# V1.net
KiCad netlist of a schematic drawn in Altium Designer
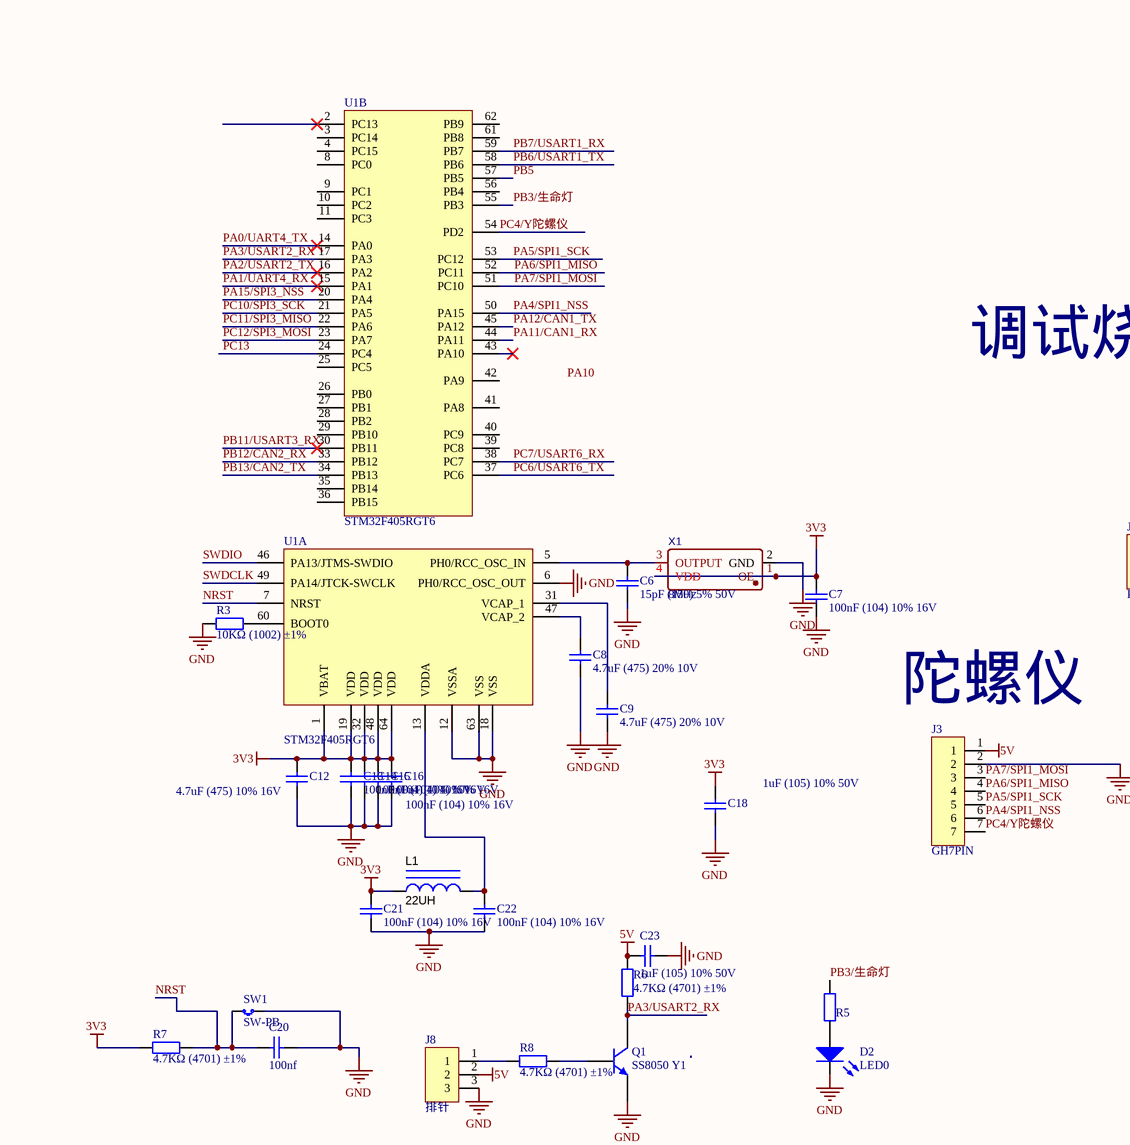
[diagram p0: 英雄云台V1.施佳良.SchDoc, top left]
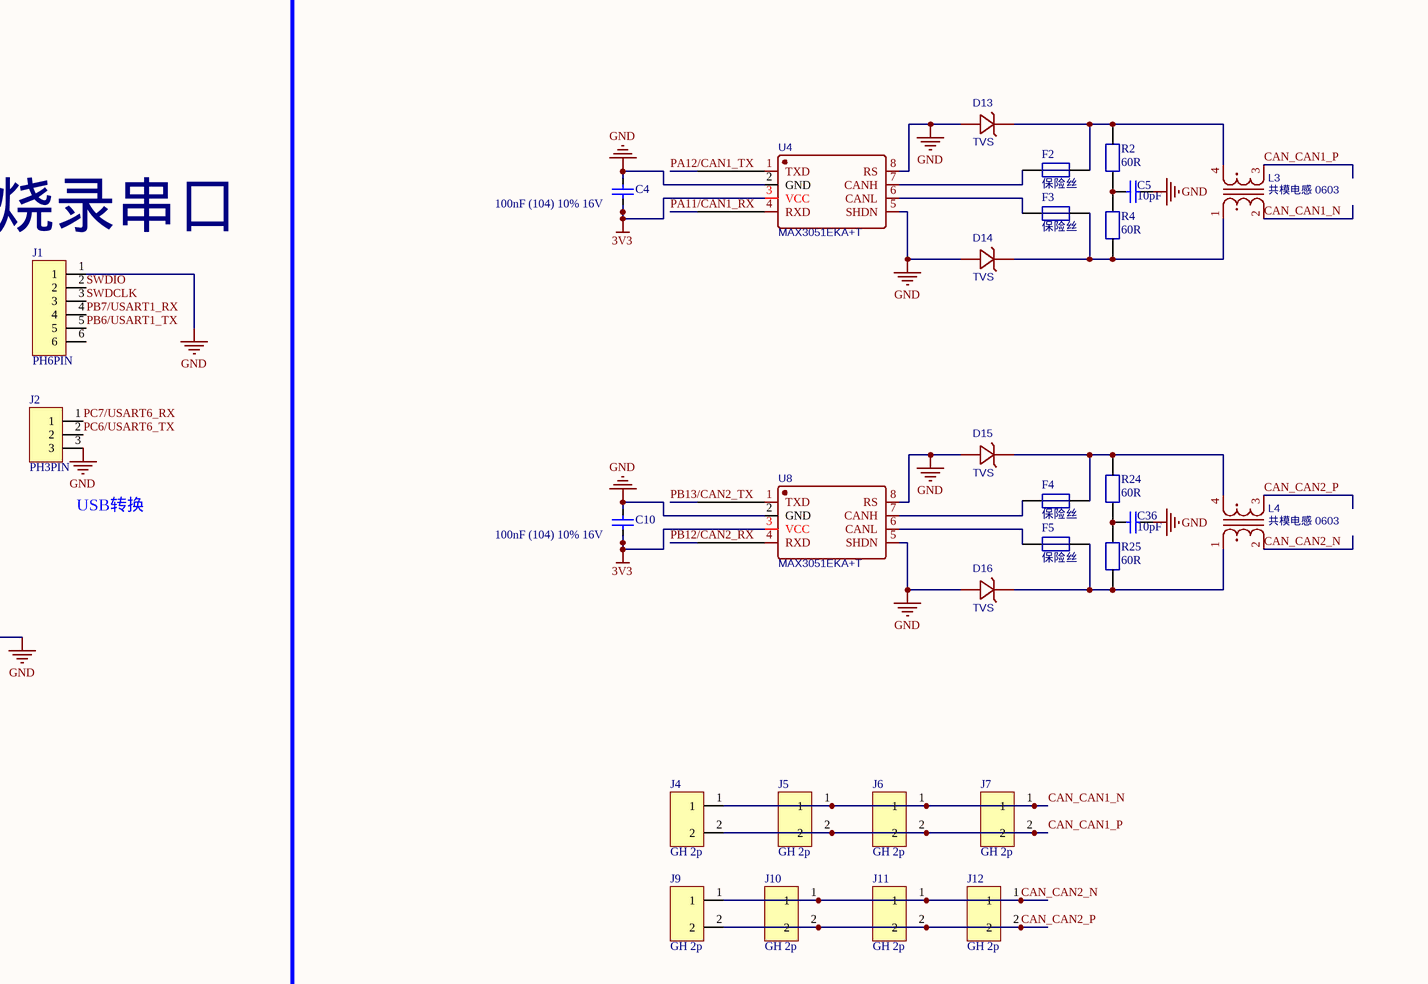
[diagram p1: 英雄云台V1.施佳良.SchDoc, top right]
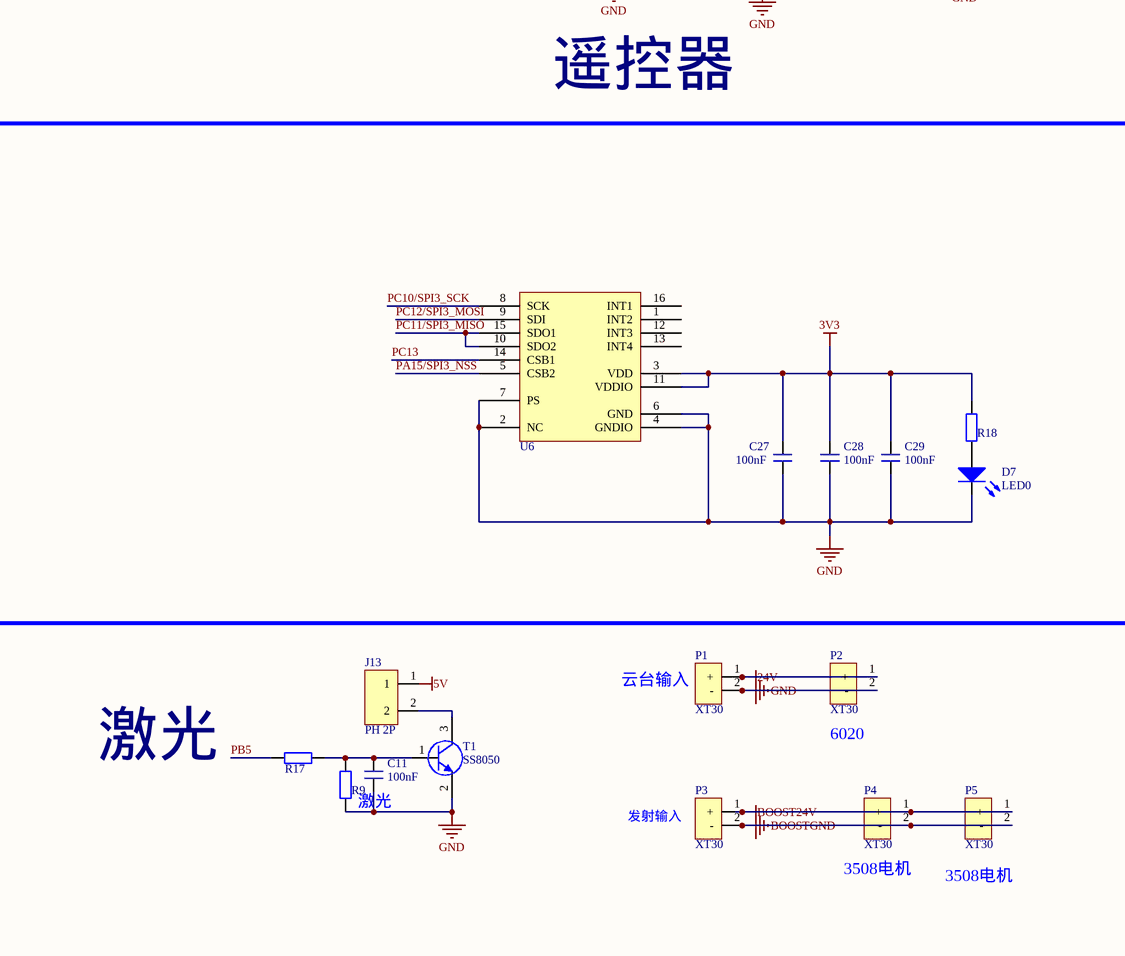
[diagram p2: 英雄云台V1.施佳良.SchDoc, bottom left]
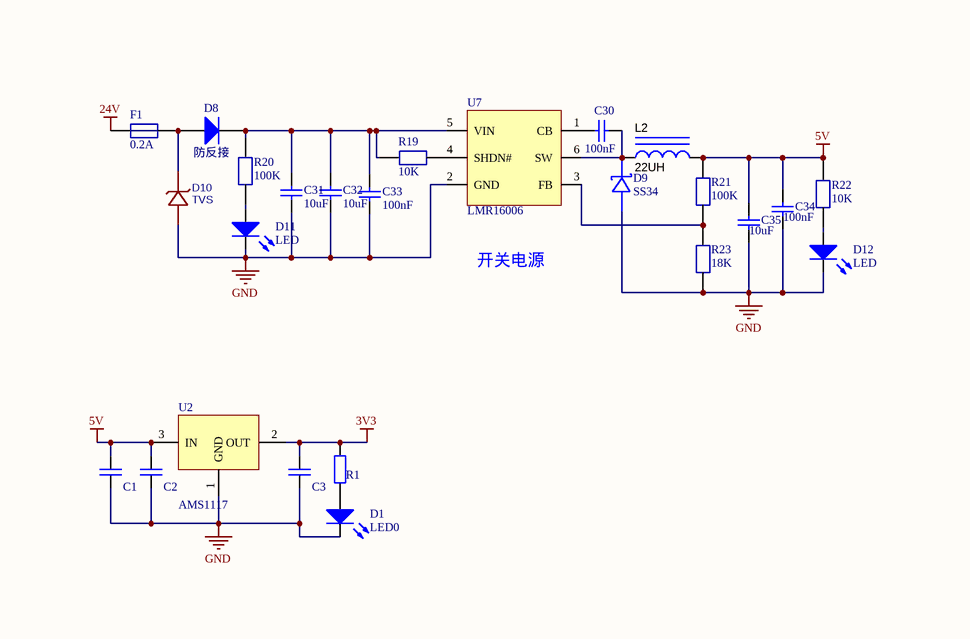
[diagram p3: 英雄云台V1.施佳良.SchDoc, bottom right]

(export (version "E")
  (design (tool "Eeschema 10.0.6"))
  (components
    (comp (ref "C1")
      (value "?uF")
      (footprint "1210_C")
      (fields (field (name "PUBLISHER") "Altium Limited"))
      (libsource (lib "电容-电阻-电感") (part "Cap"))
    )
    (comp (ref "C2")
      (value "?uF")
      (footprint "0603_C")
      (fields (field (name "PUBLISHER") "Altium Limited"))
      (libsource (lib "电容-电阻-电感") (part "Cap"))
    )
    (comp (ref "C3")
      (value "?uF")
      (footprint "1210_C")
      (fields (field (name "PUBLISHER") "Altium Limited"))
      (libsource (lib "电容-电阻-电感") (part "Cap"))
    )
    (comp (ref "C4")
      (value "100nF (104) 10% 16V")
      (footprint "0603_C")
      (description "贴片电容")
      (libsource (lib "Miscellaneous Devices LC") (part "0402 100nF (104) 10% 16V"))
    )
    (comp (ref "C5") (value "10pF") (footprint "0603_C") (libsource (lib "原理图库") (part "C")))
    (comp (ref "C6")
      (value "15pF (150) 5% 50V")
      (footprint "0603_C")
      (description "贴片电容")
      (libsource (lib "Miscellaneous Devices LC") (part "0402 15pF (150) 5% 50V"))
    )
    (comp (ref "C7")
      (value "100nF (104) 10% 16V")
      (footprint "0603_C")
      (description "贴片电容")
      (libsource (lib "Miscellaneous Devices LC") (part "0402 100nF (104) 10% 16V"))
    )
    (comp (ref "C8")
      (value "4.7uF (475) 20% 10V")
      (footprint "0603_C")
      (description "贴片电容")
      (libsource (lib "Miscellaneous Devices LC") (part "0402 4.7uF (475) 20% 10V"))
    )
    (comp (ref "C9")
      (value "4.7uF (475) 20% 10V")
      (footprint "0603_C")
      (description "贴片电容")
      (libsource (lib "Miscellaneous Devices LC") (part "0402 4.7uF (475) 20% 10V"))
    )
    (comp (ref "C10")
      (value "100nF (104) 10% 16V")
      (footprint "0603_C")
      (description "贴片电容")
      (libsource (lib "Miscellaneous Devices LC") (part "0402 100nF (104) 10% 16V"))
    )
    (comp (ref "C11")
      (value "100nF")
      (footprint "0603_C")
      (fields (field (name "PUBLISHER") "Altium Limited"))
      (libsource (lib "USUAUL") (part "Cap"))
    )
    (comp (ref "C12")
      (value "4.7uF (475) 10% 16V")
      (footprint "0603_C")
      (description "贴片电容")
      (libsource (lib "Miscellaneous Devices LC") (part "0603 4.7uF (475) 10% 16V"))
    )
    (comp (ref "C13")
      (value "100nF (104) 10% 16V")
      (footprint "0603_C")
      (description "贴片电容")
      (libsource (lib "Miscellaneous Devices LC") (part "0402 100nF (104) 10% 16V"))
    )
    (comp (ref "C14")
      (value "100nF (104) 10% 16V")
      (footprint "0603_C")
      (description "贴片电容")
      (libsource (lib "Miscellaneous Devices LC") (part "0402 100nF (104) 10% 16V"))
    )
    (comp (ref "C15")
      (value "100nF (104) 10% 16V")
      (footprint "0603_C")
      (description "贴片电容")
      (libsource (lib "Miscellaneous Devices LC") (part "0402 100nF (104) 10% 16V"))
    )
    (comp (ref "C16")
      (value "100nF (104) 10% 16V")
      (footprint "0603_C")
      (description "贴片电容")
      (libsource (lib "Miscellaneous Devices LC") (part "0402 100nF (104) 10% 16V"))
    )
    (comp (ref "C18")
      (value "1uF (105) 10% 50V")
      (footprint "0603_C")
      (description "贴片电容")
      (libsource (lib "Miscellaneous Devices LC") (part "0603 1uF (105) 10% 50V"))
    )
    (comp (ref "C20")
      (value "100nf")
      (footprint "0603_C")
      (description "贴片电容")
      (libsource (lib "Miscellaneous Devices LC") (part "0603 4.7uF (475) 10% 16V"))
    )
    (comp (ref "C21")
      (value "100nF (104) 10% 16V")
      (footprint "0603_C")
      (description "贴片电容")
      (libsource (lib "Miscellaneous Devices LC") (part "0402 100nF (104) 10% 16V"))
    )
    (comp (ref "C22")
      (value "100nF (104) 10% 16V")
      (footprint "0603_C")
      (description "贴片电容")
      (libsource (lib "Miscellaneous Devices LC") (part "0402 100nF (104) 10% 16V"))
    )
    (comp (ref "C23")
      (value "1uF (105) 10% 50V")
      (footprint "0603_C")
      (description "贴片电容")
      (libsource (lib "Miscellaneous Devices LC") (part "0603 1uF (105) 10% 50V"))
    )
    (comp (ref "C27")
      (value "100nF")
      (footprint "0603_C")
      (fields (field (name "PUBLISHER") "Altium Limited"))
      (libsource (lib "USUAUL") (part "Cap"))
    )
    (comp (ref "C28")
      (value "100nF")
      (footprint "0603_C")
      (fields (field (name "PUBLISHER") "Altium Limited"))
      (libsource (lib "USUAUL") (part "Cap"))
    )
    (comp (ref "C29")
      (value "100nF")
      (footprint "0603_C")
      (fields (field (name "PUBLISHER") "Altium Limited"))
      (libsource (lib "USUAUL") (part "Cap"))
    )
    (comp (ref "C30") (value "100nF") (footprint "0603_C") (libsource (lib "原理图库") (part "C")))
    (comp (ref "C31") (value "10uF") (footprint "1210_C") (libsource (lib "原理图库") (part "C")))
    (comp (ref "C32") (value "10uF") (footprint "1210_C") (libsource (lib "原理图库") (part "C")))
    (comp (ref "C33") (value "100nF") (footprint "0603_C") (libsource (lib "原理图库") (part "C")))
    (comp (ref "C34") (value "100nF") (footprint "0603_C") (libsource (lib "原理图库") (part "C")))
    (comp (ref "C35") (value "10uF") (footprint "1210_C") (libsource (lib "原理图库") (part "C")))
    (comp (ref "C36") (value "10pF") (footprint "0603_C") (libsource (lib "原理图库") (part "C")))
    (comp (ref "D1")
      (value "LED0")
      (footprint "LED-0603")
      (description "发光二极管")
      (fields (field (name "PUBLISHER") "Altium Limited"))
      (libsource (lib "晶体管") (part "LED0"))
    )
    (comp (ref "D2")
      (value "LED0")
      (footprint "LED-0603")
      (description "发光二极管")
      (fields (field (name "PUBLISHER") "Altium Limited"))
      (libsource (lib "晶体管") (part "LED0"))
    )
    (comp (ref "D7")
      (value "LED0")
      (footprint "LED-0603")
      (description "发光二极管")
      (fields (field (name "PUBLISHER") "Altium Limited"))
      (libsource (lib "晶体管") (part "LED0"))
    )
    (comp (ref "D8") (value "防反接") (footprint "二极管 SMAJ24A") (libsource (lib "原理图库") (part "二极管")))
    (comp (ref "D9") (value "SS34") (footprint "SOD-323") (libsource (lib "原理图库") (part "SS34")))
    (comp (ref "D10")
      (value "TVS")
      (footprint "TVS SOD-123FL_L2.8-W1.8-LS3.7-BI")
      (fields
        (field (name "BOM_SUPPLIER PART") "C669031")
        (field (name "BOM_MANUFACTURER PART") "SMAJ36A-TP")
        (field (name "CONTRIBUTOR") "LCSC")
      )
      (libsource (lib "原理图库") (part "TVS"))
    )
    (comp (ref "D11")
      (value "LED")
      (footprint "LED-0603")
      (description "发光二极管")
      (fields (field (name "PUBLISHER") "Altium Limited"))
      (libsource (lib "原理图库") (part "LED0"))
    )
    (comp (ref "D12")
      (value "LED")
      (footprint "LED-0603")
      (description "发光二极管")
      (fields (field (name "PUBLISHER") "Altium Limited"))
      (libsource (lib "原理图库") (part "LED0"))
    )
    (comp (ref "D13")
      (value "TVS")
      (footprint "TVS SOD-323")
      (fields
        (field (name "BOM_SUPPLIER PART") "C669031")
        (field (name "BOM_MANUFACTURER PART") "SMAJ36A-TP")
        (field (name "CONTRIBUTOR") "LCSC")
      )
      (libsource (lib "原理图库") (part "TVS"))
    )
    (comp (ref "D14")
      (value "TVS")
      (footprint "TVS SOD-323")
      (fields
        (field (name "BOM_SUPPLIER PART") "C669031")
        (field (name "BOM_MANUFACTURER PART") "SMAJ36A-TP")
        (field (name "CONTRIBUTOR") "LCSC")
      )
      (libsource (lib "原理图库") (part "TVS"))
    )
    (comp (ref "D15")
      (value "TVS")
      (footprint "TVS SOD-323")
      (fields
        (field (name "BOM_SUPPLIER PART") "C669031")
        (field (name "BOM_MANUFACTURER PART") "SMAJ36A-TP")
        (field (name "CONTRIBUTOR") "LCSC")
      )
      (libsource (lib "原理图库") (part "TVS"))
    )
    (comp (ref "D16")
      (value "TVS")
      (footprint "TVS SOD-323")
      (fields
        (field (name "BOM_SUPPLIER PART") "C669031")
        (field (name "BOM_MANUFACTURER PART") "SMAJ36A-TP")
        (field (name "CONTRIBUTOR") "LCSC")
      )
      (libsource (lib "原理图库") (part "TVS"))
    )
    (comp (ref "F1") (value "0.2A") (footprint "保险丝 F1812") (libsource (lib "原理图库") (part "保险丝")))
    (comp (ref "F2") (value "保险丝") (footprint "保险丝 F0603") (libsource (lib "原理图库") (part "保险丝")))
    (comp (ref "F3") (value "保险丝") (footprint "保险丝 F0603") (libsource (lib "原理图库") (part "保险丝")))
    (comp (ref "F4") (value "保险丝") (footprint "保险丝 F0603") (libsource (lib "原理图库") (part "保险丝")))
    (comp (ref "F5") (value "保险丝") (footprint "保险丝 F0603") (libsource (lib "原理图库") (part "保险丝")))
    (comp (ref "J1") (value "PH6PIN") (footprint "PH 6P(DIP)") (libsource (lib "连接器") (part "PH 6P")))
    (comp (ref "J2") (value "PH3PIN") (footprint "PH 3P(DIP)") (libsource (lib "连接器") (part "PH 3P")))
    (comp (ref "J3")
      (value "GH7PIN")
      (footprint "GH 7P 1.25mm 立 贴")
      (libsource (lib "YXIONG") (part "GH 7PIN"))
    )
    (comp (ref "J4") (value "GH 2p") (footprint "GH 2P 立") (libsource (lib "连接器") (part "GH 2p")))
    (comp (ref "J5") (value "GH 2p") (footprint "GH 2P 立") (libsource (lib "连接器") (part "GH 2p")))
    (comp (ref "J6") (value "GH 2p") (footprint "GH 2P 立") (libsource (lib "连接器") (part "GH 2p")))
    (comp (ref "J7") (value "GH 2p") (footprint "GH 2P 立") (libsource (lib "连接器") (part "GH 2p")))
    (comp (ref "J8") (value "排针") (footprint "SIP3") (libsource (lib "连接器") (part "PH 3P")))
    (comp (ref "J9") (value "GH 2p") (footprint "GH 2P 立") (libsource (lib "连接器") (part "GH 2p")))
    (comp (ref "J10") (value "GH 2p") (footprint "GH 2P 立") (libsource (lib "连接器") (part "GH 2p")))
    (comp (ref "J11") (value "GH 2p") (footprint "GH 2P 立") (libsource (lib "连接器") (part "GH 2p")))
    (comp (ref "J12") (value "GH 2p") (footprint "GH 2P 立") (libsource (lib "连接器") (part "GH 2p")))
    (comp (ref "J13") (value "PH 2P") (footprint "PH 2P(DIP)") (libsource (lib "连接器") (part "PH 2P")))
    (comp (ref "L1")
      (value "LPS4018-333MLB")
      (footprint "0603_R")
      (description "Inductor, Shielded Drum Core, Ferrite, 33 µH, 0.68 A, 0.42 ohm, SMD")
      (fields
        (field (name "MANUFACTURER") "Coilcraft")
        (field (name "VALUEDISPLAYED") "22UH")
        (field (name "PUBLISHER") "Texas Instruments")
      )
      (libsource (lib "原理图库") (part "电感"))
    )
    (comp (ref "L2")
      (value "LPS4018-333MLB")
      (footprint "电感 (IND-SMD_L7.1-W6.6)")
      (description "Inductor, Shielded Drum Core, Ferrite, 33 µH, 0.68 A, 0.42 ohm, SMD")
      (fields
        (field (name "MANUFACTURER") "Coilcraft")
        (field (name "VALUEDISPLAYED") "22UH")
        (field (name "PUBLISHER") "Texas Instruments")
      )
      (libsource (lib "原理图库") (part "电感"))
    )
    (comp (ref "L3")
      (value "共模电感 0603")
      (footprint "共模电感 IND-SMD_4P-L2.0-W1.2")
      (fields
        (field (name "BOM_SUPPLIER PART") "C329447")
        (field (name "BOM_MANUFACTURER PART") "SCM2012F-181M-I-LRH")
        (field (name "CONTRIBUTOR") "LCSC")
      )
      (libsource (lib "原理图库") (part "共模电感 0603"))
    )
    (comp (ref "L4")
      (value "共模电感 0603")
      (footprint "共模电感 IND-SMD_4P-L2.0-W1.2")
      (fields
        (field (name "BOM_SUPPLIER PART") "C329447")
        (field (name "BOM_MANUFACTURER PART") "SCM2012F-181M-I-LRH")
        (field (name "CONTRIBUTOR") "LCSC")
      )
      (libsource (lib "原理图库") (part "共模电感 0603"))
    )
    (comp (ref "P1") (value "XT30") (footprint "XT30PW公") (libsource (lib "连接器") (part "XT30")))
    (comp (ref "P2") (value "XT30") (footprint "XT30 cewo") (libsource (lib "连接器") (part "XT30")))
    (comp (ref "P3") (value "XT30") (footprint "XT30PW公") (libsource (lib "连接器") (part "XT30")))
    (comp (ref "P4") (value "XT30") (footprint "真对线XT30") (libsource (lib "连接器") (part "XT30")))
    (comp (ref "P5") (value "XT30") (footprint "真对线XT30") (libsource (lib "连接器") (part "XT30")))
    (comp (ref "Q1")
      (value "SS8050 Y1")
      (footprint "SOT-23(SOT-23-3)")
      (description "三极管")
      (libsource (lib "Miscellaneous Devices LC") (part "SOT-23 SS8050 Y1"))
    )
    (comp (ref "R1")
      (value "10k")
      (footprint "0603_R")
      (fields (field (name "PUBLISHER") "Altium Limited"))
      (libsource (lib "电容-电阻-电感") (part "Res"))
    )
    (comp (ref "R2") (value "60R") (footprint "0603_R") (libsource (lib "原理图库") (part "R")))
    (comp (ref "R3")
      (value "10KΩ (1002) ±1%")
      (footprint "0603_R")
      (description "贴片电阻")
      (libsource (lib "Miscellaneous Devices LC") (part "0402 10KΩ (1002) 1%"))
    )
    (comp (ref "R4") (value "60R") (footprint "0603_R") (libsource (lib "原理图库") (part "R")))
    (comp (ref "R5")
      (value "10k")
      (footprint "0603_R")
      (fields (field (name "PUBLISHER") "Altium Limited"))
      (libsource (lib "电容-电阻-电感") (part "Res"))
    )
    (comp (ref "R6")
      (value "4.7KΩ (4701) ±1%")
      (footprint "0603_R")
      (description "贴片电阻")
      (libsource (lib "Miscellaneous Devices LC") (part "0603 4.7KΩ (4701) 1%"))
    )
    (comp (ref "R7")
      (value "4.7KΩ (4701) ±1%")
      (footprint "0603_R")
      (description "贴片电阻")
      (libsource (lib "") (part "0603 4.7KΩ (4701) 1%_1"))
    )
    (comp (ref "R8")
      (value "4.7KΩ (4701) ±1%")
      (footprint "0603_R")
      (description "贴片电阻")
      (libsource (lib "") (part "0603 4.7KΩ (4701) 1%_1"))
    )
    (comp (ref "R9")
      (value "Res")
      (footprint "0603_R")
      (fields (field (name "PUBLISHER") "Altium Limited"))
      (libsource (lib "") (part "Res_1"))
    )
    (comp (ref "R17")
      (value "Res")
      (footprint "0603_R")
      (fields (field (name "PUBLISHER") "Altium Limited"))
      (libsource (lib "") (part "Res_2"))
    )
    (comp (ref "R18")
      (value "10k")
      (footprint "0603_R")
      (fields (field (name "PUBLISHER") "Altium Limited"))
      (libsource (lib "电容-电阻-电感") (part "Res"))
    )
    (comp (ref "R19") (value "10K") (footprint "0603_R") (libsource (lib "原理图库") (part "R")))
    (comp (ref "R20") (value "100K") (footprint "0603_R") (libsource (lib "原理图库") (part "R")))
    (comp (ref "R21") (value "100K") (footprint "0603_R") (libsource (lib "原理图库") (part "R")))
    (comp (ref "R22") (value "10K") (footprint "0603_R") (libsource (lib "原理图库") (part "R")))
    (comp (ref "R23") (value "18K") (footprint "0603_R") (libsource (lib "原理图库") (part "R")))
    (comp (ref "R24") (value "60R") (footprint "0603_R") (libsource (lib "原理图库") (part "R")))
    (comp (ref "R25") (value "60R") (footprint "0603_R") (libsource (lib "原理图库") (part "R")))
    (comp (ref "SW1") (value "SW-PB") (footprint "按键") (libsource (lib "stm32") (part "SW-PB")))
    (comp (ref "T1")
      (value "SS8050")
      (footprint "SOT_23")
      (description "NPN")
      (fields (field (name "PUBLISHER") "Altium Limited"))
      (libsource (lib "二极管-晶体管") (part "SS8050"))
    )
    (comp (ref "U1")
      (value "STM32F405RGT6")
      (footprint "LC-LQFP-64_10x10x05P")
      (libsource (lib "") (part "STM32F405RGT6_1"))
    )
    (comp (ref "U2")
      (value "AMS1117")
      (footprint "SOT-223")
      (description "线性稳压3.3V-5V 1A")
      (libsource (lib "电源-电路保护") (part "AMS1117"))
    )
    (comp (ref "U4")
      (value "MAX3051EKA+T")
      (footprint "SOIC-8_L4.9-W3.9-P1.27-LS6.0-BL")
      (fields (field (name "BOM_SUPPLIER PART") "C112005"))
      (libsource (lib "原理图库") (part "MAX3051EKA+T"))
    )
    (comp (ref "U6") (value "dmi088") (footprint "DMI088") (libsource (lib "dmi088") (part "dmi088")))
    (comp (ref "U7")
      (value "LMR16006")
      (footprint "开关电源 (LMR16006)")
      (libsource (lib "原理图库") (part "LMR16006"))
    )
    (comp (ref "U8")
      (value "MAX3051EKA+T")
      (footprint "SOIC-8_L4.9-W3.9-P1.27-LS6.0-BL")
      (fields (field (name "BOM_SUPPLIER PART") "C112005"))
      (libsource (lib "原理图库") (part "MAX3051EKA+T"))
    )
    (comp (ref "X1")
      (value "8MHz")
      (footprint "OSC-SMD_4P-L2.5-W2.0-BL")
      (fields
        (field (name "BOM_SUPPLIER PART") "C390520")
        (field (name "BOM_MANUFACTURER PART") "SG-8018CG-8.000000MHz-TJHSA")
        (field (name "CONTRIBUTOR") "LCSC")
      )
      (libsource (lib "Schlib2") (part "8MHz"))
    )
  )
  (nets
    (net (code "1") (name "/CAN_CAN1_N") (class "Default")
      (node (ref "J4") (pin "1") (pinfunction "1_1") (pintype "power_in"))
      (node (ref "J5") (pin "1") (pinfunction "1_1") (pintype "power_in"))
      (node (ref "J6") (pin "1") (pinfunction "1_1") (pintype "power_in"))
      (node (ref "J7") (pin "1") (pinfunction "1_1") (pintype "power_in"))
      (node (ref "L3") (pin "2") (pinfunction "2_2") (pintype "passive"))
    )
    (net (code "2") (name "/CAN_CAN1_P") (class "Default")
      (node (ref "J4") (pin "2") (pinfunction "2_2") (pintype "passive"))
      (node (ref "J5") (pin "2") (pinfunction "2_2") (pintype "passive"))
      (node (ref "J6") (pin "2") (pinfunction "2_2") (pintype "passive"))
      (node (ref "J7") (pin "2") (pinfunction "2_2") (pintype "passive"))
      (node (ref "L3") (pin "3") (pinfunction "3_3") (pintype "passive"))
    )
    (net (code "3") (name "/CAN_CAN2_N") (class "Default")
      (node (ref "J10") (pin "1") (pinfunction "1_1") (pintype "power_in"))
      (node (ref "J11") (pin "1") (pinfunction "1_1") (pintype "power_in"))
      (node (ref "J12") (pin "1") (pinfunction "1_1") (pintype "power_in"))
      (node (ref "J9") (pin "1") (pinfunction "1_1") (pintype "power_in"))
      (node (ref "L4") (pin "2") (pinfunction "2_2") (pintype "passive"))
    )
    (net (code "4") (name "/CAN_CAN2_P") (class "Default")
      (node (ref "J10") (pin "2") (pinfunction "2_2") (pintype "passive"))
      (node (ref "J11") (pin "2") (pinfunction "2_2") (pintype "passive"))
      (node (ref "J12") (pin "2") (pinfunction "2_2") (pintype "passive"))
      (node (ref "J9") (pin "2") (pinfunction "2_2") (pintype "passive"))
      (node (ref "L4") (pin "3") (pinfunction "3_3") (pintype "passive"))
    )
    (net (code "5") (name "/NRST") (class "Default")
      (node (ref "C20") (pin "2") (pinfunction "2_2") (pintype "passive"))
      (node (ref "R7") (pin "2") (pinfunction "2_2") (pintype "passive"))
      (node (ref "SW1") (pin "1") (pinfunction "1_1") (pintype "passive"))
      (node (ref "U1") (pin "7") (pinfunction "NRST_7") (pintype "passive"))
    )
    (net (code "6") (name "/PA0{slash}UART4_TX") (class "Default")
      (node (ref "U1") (pin "14") (pinfunction "PA0_14") (pintype "passive+no_connect"))
    )
    (net (code "7") (name "/PA1{slash}UART4_RX") (class "Default")
      (node (ref "U1") (pin "15") (pinfunction "PA1_15") (pintype "passive+no_connect"))
    )
    (net (code "8") (name "/PA2{slash}USART2_TX") (class "Default")
      (node (ref "U1") (pin "16") (pinfunction "PA2_16") (pintype "passive+no_connect"))
    )
    (net (code "9") (name "/PA3{slash}USART2_RX") (class "Default")
      (node (ref "Q1") (pin "3") (pinfunction "C_3") (pintype "passive"))
      (node (ref "R6") (pin "1") (pinfunction "1_1") (pintype "passive"))
      (node (ref "U1") (pin "17") (pinfunction "PA3_17") (pintype "passive"))
    )
    (net (code "10") (name "/PA4{slash}SPI1_NSS") (class "Default")
      (node (ref "J3") (pin "6") (pinfunction "6_6") (pintype "passive"))
      (node (ref "U1") (pin "50") (pinfunction "PA15_50") (pintype "passive"))
    )
    (net (code "11") (name "/PA5{slash}SPI1_SCK") (class "Default")
      (node (ref "J3") (pin "5") (pinfunction "5_5") (pintype "passive"))
      (node (ref "U1") (pin "53") (pinfunction "PC12_53") (pintype "passive"))
    )
    (net (code "12") (name "/PA6{slash}SPI1_MISO") (class "Default")
      (node (ref "J3") (pin "4") (pinfunction "4_4") (pintype "passive"))
      (node (ref "U1") (pin "52") (pinfunction "PC11_52") (pintype "passive"))
    )
    (net (code "13") (name "/PA7{slash}SPI1_MOSI") (class "Default")
      (node (ref "J3") (pin "3") (pinfunction "3_3") (pintype "passive"))
      (node (ref "U1") (pin "51") (pinfunction "PC10_51") (pintype "passive"))
    )
    (net (code "15") (name "/PA11{slash}CAN1_RX") (class "Default")
      (node (ref "U1") (pin "44") (pinfunction "PA11_44") (pintype "passive"))
      (node (ref "U4") (pin "4") (pinfunction "RXD_4") (pintype "passive"))
    )
    (net (code "16") (name "/PA12{slash}CAN1_TX") (class "Default")
      (node (ref "U1") (pin "45") (pinfunction "PA12_45") (pintype "passive"))
      (node (ref "U4") (pin "1") (pinfunction "TXD_1") (pintype "passive"))
    )
    (net (code "17") (name "/PA15{slash}SPI3_NSS") (class "Default")
      (node (ref "U1") (pin "20") (pinfunction "PA4_20") (pintype "passive"))
      (node (ref "U6") (pin "5") (pinfunction "CSB2_5") (pintype "passive"))
    )
    (net (code "18") (name "/PB3{slash}生命灯") (class "Default")
      (node (ref "R5") (pin "2") (pinfunction "2_2") (pintype "passive"))
      (node (ref "U1") (pin "55") (pinfunction "PB3_55") (pintype "passive"))
    )
    (net (code "19") (name "/PB5") (class "Default")
      (node (ref "R17") (pin "1") (pinfunction "1_1") (pintype "passive"))
      (node (ref "U1") (pin "57") (pinfunction "PB5_57") (pintype "passive"))
    )
    (net (code "20") (name "/PB6{slash}USART1_TX") (class "Default")
      (node (ref "J1") (pin "5") (pinfunction "5_5") (pintype "passive"))
      (node (ref "U1") (pin "58") (pinfunction "PB6_58") (pintype "passive"))
    )
    (net (code "21") (name "/PB7{slash}USART1_RX") (class "Default")
      (node (ref "J1") (pin "4") (pinfunction "4_4") (pintype "passive"))
      (node (ref "U1") (pin "59") (pinfunction "PB7_59") (pintype "passive"))
    )
    (net (code "22") (name "/PB11{slash}USART3_RX") (class "Default")
      (node (ref "U1") (pin "30") (pinfunction "PB11_30") (pintype "open_collector+no_connect"))
    )
    (net (code "23") (name "/PB12{slash}CAN2_RX") (class "Default")
      (node (ref "U1") (pin "33") (pinfunction "PB12_33") (pintype "passive"))
      (node (ref "U8") (pin "4") (pinfunction "RXD_4") (pintype "passive"))
    )
    (net (code "24") (name "/PB13{slash}CAN2_TX") (class "Default")
      (node (ref "U1") (pin "34") (pinfunction "PB13_34") (pintype "passive"))
      (node (ref "U8") (pin "1") (pinfunction "TXD_1") (pintype "passive"))
    )
    (net (code "25") (name "/PC4{slash}Y陀螺仪") (class "Default")
      (node (ref "J3") (pin "7") (pinfunction "7_7") (pintype "passive"))
      (node (ref "U1") (pin "54") (pinfunction "PD2_54") (pintype "passive"))
    )
    (net (code "26") (name "/PC6{slash}USART6_TX") (class "Default")
      (node (ref "J2") (pin "2") (pinfunction "2_2") (pintype "power_in"))
      (node (ref "U1") (pin "37") (pinfunction "PC6_37") (pintype "passive"))
    )
    (net (code "27") (name "/PC7{slash}USART6_RX") (class "Default")
      (node (ref "J2") (pin "1") (pinfunction "1_1") (pintype "power_in"))
      (node (ref "U1") (pin "38") (pinfunction "PC7_38") (pintype "passive"))
    )
    (net (code "28") (name "/PC10{slash}SPI3_SCK") (class "Default")
      (node (ref "U1") (pin "21") (pinfunction "PA5_21") (pintype "passive"))
      (node (ref "U6") (pin "8") (pinfunction "SCK_8") (pintype "passive"))
    )
    (net (code "29") (name "/PC11{slash}SPI3_MISO") (class "Default")
      (node (ref "U1") (pin "22") (pinfunction "PA6_22") (pintype "passive"))
      (node (ref "U6") (pin "10") (pinfunction "SDO2_10") (pintype "passive"))
      (node (ref "U6") (pin "15") (pinfunction "SDO1_15") (pintype "passive"))
    )
    (net (code "30") (name "/PC12{slash}SPI3_MOSI") (class "Default")
      (node (ref "U1") (pin "23") (pinfunction "PA7_23") (pintype "passive"))
      (node (ref "U6") (pin "9") (pinfunction "SDI_9") (pintype "passive"))
    )
    (net (code "31") (name "/PC13") (class "Default")
      (node (ref "U1") (pin "24") (pinfunction "PC4_24") (pintype "passive"))
      (node (ref "U6") (pin "14") (pinfunction "CSB1_14") (pintype "passive"))
    )
    (net (code "32") (name "/SWDCLK") (class "Default")
      (node (ref "J1") (pin "3") (pinfunction "3_3") (pintype "passive"))
      (node (ref "U1") (pin "49") (pinfunction "PA14/JTCK-SWCLK_49") (pintype "passive"))
    )
    (net (code "33") (name "/SWDIO") (class "Default")
      (node (ref "J1") (pin "2") (pinfunction "2_2") (pintype "passive"))
      (node (ref "U1") (pin "46") (pinfunction "PA13/JTMS-SWDIO_46") (pintype "passive"))
    )
    (net (code "34") (name "3V3") (class "Default")
      (node (ref "C10") (pin "1") (pinfunction "1_1") (pintype "passive"))
      (node (ref "C12") (pin "2") (pinfunction "2_2") (pintype "passive"))
      (node (ref "C13") (pin "2") (pinfunction "2_2") (pintype "passive"))
      (node (ref "C14") (pin "2") (pinfunction "2_2") (pintype "passive"))
      (node (ref "C15") (pin "2") (pinfunction "2_2") (pintype "passive"))
      (node (ref "C16") (pin "2") (pinfunction "2_2") (pintype "passive"))
      (node (ref "C18") (pin "2") (pinfunction "2_2") (pintype "passive"))
      (node (ref "C21") (pin "2") (pinfunction "2_2") (pintype "passive"))
      (node (ref "C27") (pin "2") (pinfunction "2_2") (pintype "passive"))
      (node (ref "C28") (pin "2") (pinfunction "2_2") (pintype "passive"))
      (node (ref "C29") (pin "2") (pinfunction "2_2") (pintype "passive"))
      (node (ref "C3") (pin "2") (pinfunction "2_2") (pintype "passive"))
      (node (ref "C4") (pin "1") (pinfunction "1_1") (pintype "passive"))
      (node (ref "C7") (pin "2") (pinfunction "2_2") (pintype "passive"))
      (node (ref "L1") (pin "1") (pinfunction "1_1") (pintype "passive"))
      (node (ref "R1") (pin "2") (pinfunction "2_2") (pintype "passive"))
      (node (ref "R18") (pin "2") (pinfunction "2_2") (pintype "passive"))
      (node (ref "R7") (pin "1") (pinfunction "1_1") (pintype "passive"))
      (node (ref "U1") (pin "1") (pinfunction "VBAT_1") (pintype "passive"))
      (node (ref "U1") (pin "19") (pinfunction "VDD_19") (pintype "passive"))
      (node (ref "U1") (pin "32") (pinfunction "VDD_32") (pintype "passive"))
      (node (ref "U1") (pin "48") (pinfunction "VDD_48") (pintype "passive"))
      (node (ref "U1") (pin "64") (pinfunction "VDD_64") (pintype "passive"))
      (node (ref "U2") (pin "2") (pinfunction "OUT_2") (pintype "passive"))
      (node (ref "U4") (pin "3") (pinfunction "VCC_3") (pintype "passive"))
      (node (ref "U6") (pin "11") (pinfunction "VDDIO_11") (pintype "passive"))
      (node (ref "U6") (pin "3") (pinfunction "VDD_3") (pintype "passive"))
      (node (ref "U8") (pin "3") (pinfunction "VCC_3") (pintype "passive"))
      (node (ref "X1") (pin "1") (pinfunction "OE_1") (pintype "passive"))
      (node (ref "X1") (pin "4") (pinfunction "VDD_4") (pintype "passive"))
    )
    (net (code "35") (name "5V") (class "Default")
      (node (ref "C1") (pin "2") (pinfunction "2_2") (pintype "passive"))
      (node (ref "C2") (pin "2") (pinfunction "2_2") (pintype "passive"))
      (node (ref "C23") (pin "1") (pinfunction "1_1") (pintype "passive"))
      (node (ref "C34") (pin "1") (pinfunction "1_1") (pintype "passive"))
      (node (ref "C35") (pin "1") (pinfunction "1_1") (pintype "passive"))
      (node (ref "J13") (pin "1") (pinfunction "1_1") (pintype "power_in"))
      (node (ref "J3") (pin "1") (pinfunction "1_1") (pintype "passive"))
      (node (ref "J8") (pin "2") (pinfunction "2_2") (pintype "power_in"))
      (node (ref "L2") (pin "2") (pinfunction "2_2") (pintype "passive"))
      (node (ref "R21") (pin "1") (pinfunction "1_1") (pintype "passive"))
      (node (ref "R22") (pin "1") (pinfunction "1_1") (pintype "passive"))
      (node (ref "R6") (pin "2") (pinfunction "2_2") (pintype "passive"))
      (node (ref "U2") (pin "3") (pinfunction "IN_3") (pintype "passive"))
    )
    (net (code "36") (name "24V") (class "Default")
      (node (ref "F1") (pin "1") (pinfunction "1_1") (pintype "passive"))
      (node (ref "P1") (pin "1") (pinfunction "+_1") (pintype "passive"))
      (node (ref "P2") (pin "1") (pinfunction "+_1") (pintype "passive"))
    )
    (net (code "37") (name "BOOST24V") (class "Default")
      (node (ref "P3") (pin "1") (pinfunction "+_1") (pintype "passive"))
      (node (ref "P4") (pin "1") (pinfunction "+_1") (pintype "passive"))
      (node (ref "P5") (pin "1") (pinfunction "+_1") (pintype "passive"))
    )
    (net (code "38") (name "BOOSTGND") (class "Default")
      (node (ref "P3") (pin "2") (pinfunction "-_2") (pintype "passive"))
      (node (ref "P4") (pin "2") (pinfunction "-_2") (pintype "passive"))
      (node (ref "P5") (pin "2") (pinfunction "-_2") (pintype "passive"))
    )
    (net (code "39") (name "GND") (class "Default")
      (node (ref "C1") (pin "1") (pinfunction "1_1") (pintype "passive"))
      (node (ref "C10") (pin "2") (pinfunction "2_2") (pintype "passive"))
      (node (ref "C11") (pin "1") (pinfunction "1_1") (pintype "passive"))
      (node (ref "C12") (pin "1") (pinfunction "1_1") (pintype "passive"))
      (node (ref "C13") (pin "1") (pinfunction "1_1") (pintype "passive"))
      (node (ref "C14") (pin "1") (pinfunction "1_1") (pintype "passive"))
      (node (ref "C15") (pin "1") (pinfunction "1_1") (pintype "passive"))
      (node (ref "C16") (pin "1") (pinfunction "1_1") (pintype "passive"))
      (node (ref "C18") (pin "1") (pinfunction "1_1") (pintype "passive"))
      (node (ref "C2") (pin "1") (pinfunction "1_1") (pintype "passive"))
      (node (ref "C20") (pin "1") (pinfunction "1_1") (pintype "passive"))
      (node (ref "C21") (pin "1") (pinfunction "1_1") (pintype "passive"))
      (node (ref "C22") (pin "1") (pinfunction "1_1") (pintype "passive"))
      (node (ref "C23") (pin "2") (pinfunction "2_2") (pintype "passive"))
      (node (ref "C27") (pin "1") (pinfunction "1_1") (pintype "passive"))
      (node (ref "C28") (pin "1") (pinfunction "1_1") (pintype "passive"))
      (node (ref "C29") (pin "1") (pinfunction "1_1") (pintype "passive"))
      (node (ref "C3") (pin "1") (pinfunction "1_1") (pintype "passive"))
      (node (ref "C31") (pin "2") (pinfunction "2_2") (pintype "passive"))
      (node (ref "C32") (pin "2") (pinfunction "2_2") (pintype "passive"))
      (node (ref "C33") (pin "2") (pinfunction "2_2") (pintype "passive"))
      (node (ref "C34") (pin "2") (pinfunction "2_2") (pintype "passive"))
      (node (ref "C35") (pin "2") (pinfunction "2_2") (pintype "passive"))
      (node (ref "C36") (pin "2") (pinfunction "2_2") (pintype "passive"))
      (node (ref "C4") (pin "2") (pinfunction "2_2") (pintype "passive"))
      (node (ref "C5") (pin "2") (pinfunction "2_2") (pintype "passive"))
      (node (ref "C6") (pin "1") (pinfunction "1_1") (pintype "passive"))
      (node (ref "C7") (pin "1") (pinfunction "1_1") (pintype "passive"))
      (node (ref "C8") (pin "1") (pinfunction "1_1") (pintype "passive"))
      (node (ref "C9") (pin "1") (pinfunction "1_1") (pintype "passive"))
      (node (ref "D1") (pin "2") (pinfunction "K_2") (pintype "passive"))
      (node (ref "D10") (pin "2") (pinfunction "A_2") (pintype "passive"))
      (node (ref "D11") (pin "2") (pinfunction "K_2") (pintype "passive"))
      (node (ref "D12") (pin "2") (pinfunction "K_2") (pintype "passive"))
      (node (ref "D13") (pin "2") (pinfunction "A_2") (pintype "passive"))
      (node (ref "D14") (pin "2") (pinfunction "A_2") (pintype "passive"))
      (node (ref "D15") (pin "2") (pinfunction "A_2") (pintype "passive"))
      (node (ref "D16") (pin "2") (pinfunction "A_2") (pintype "passive"))
      (node (ref "D2") (pin "2") (pinfunction "K_2") (pintype "passive"))
      (node (ref "D7") (pin "2") (pinfunction "K_2") (pintype "passive"))
      (node (ref "D9") (pin "2") (pinfunction "A_2") (pintype "passive"))
      (node (ref "J1") (pin "1") (pinfunction "1_1") (pintype "passive"))
      (node (ref "J2") (pin "3") (pinfunction "3_3") (pintype "power_in"))
      (node (ref "J3") (pin "2") (pinfunction "2_2") (pintype "passive"))
      (node (ref "J8") (pin "3") (pinfunction "3_3") (pintype "power_in"))
      (node (ref "P1") (pin "2") (pinfunction "-_2") (pintype "passive"))
      (node (ref "P2") (pin "2") (pinfunction "-_2") (pintype "passive"))
      (node (ref "Q1") (pin "2") (pinfunction "E_2") (pintype "passive"))
      (node (ref "R23") (pin "2") (pinfunction "2_2") (pintype "passive"))
      (node (ref "R3") (pin "1") (pinfunction "1_1") (pintype "passive"))
      (node (ref "R9") (pin "1") (pinfunction "1_1") (pintype "passive"))
      (node (ref "SW1") (pin "2") (pinfunction "2_2") (pintype "passive"))
      (node (ref "T1") (pin "2") (pinfunction "E_2") (pintype "passive"))
      (node (ref "U1") (pin "12") (pinfunction "VSSA_12") (pintype "passive"))
      (node (ref "U1") (pin "18") (pinfunction "VSS_18") (pintype "passive"))
      (node (ref "U1") (pin "6") (pinfunction "PH0/RCC_OSC_OUT_6") (pintype "passive"))
      (node (ref "U1") (pin "63") (pinfunction "VSS_63") (pintype "passive"))
      (node (ref "U2") (pin "1") (pinfunction "GND_1") (pintype "passive"))
      (node (ref "U4") (pin "2") (pinfunction "GND_2") (pintype "passive"))
      (node (ref "U4") (pin "5") (pinfunction "SHDN_5") (pintype "passive"))
      (node (ref "U4") (pin "8") (pinfunction "RS_8") (pintype "passive"))
      (node (ref "U6") (pin "2") (pinfunction "NC_2") (pintype "passive"))
      (node (ref "U6") (pin "4") (pinfunction "GNDIO_4") (pintype "passive"))
      (node (ref "U6") (pin "6") (pinfunction "GND_6") (pintype "passive"))
      (node (ref "U6") (pin "7") (pinfunction "PS_7") (pintype "passive"))
      (node (ref "U7") (pin "2") (pinfunction "GND_2") (pintype "passive"))
      (node (ref "U8") (pin "2") (pinfunction "GND_2") (pintype "passive"))
      (node (ref "U8") (pin "5") (pinfunction "SHDN_5") (pintype "passive"))
      (node (ref "U8") (pin "8") (pinfunction "RS_8") (pintype "passive"))
      (node (ref "X1") (pin "2") (pinfunction "GND_2") (pintype "passive"))
    )
    (net (code "40") (name "Net-(C5-Pad1)") (class "Default")
      (node (ref "C5") (pin "1") (pinfunction "1_1") (pintype "passive"))
      (node (ref "R2") (pin "1") (pinfunction "1_1") (pintype "passive"))
      (node (ref "R4") (pin "1") (pinfunction "1_1") (pintype "passive"))
    )
    (net (code "41") (name "Net-(C36-Pad1)") (class "Default")
      (node (ref "C36") (pin "1") (pinfunction "1_1") (pintype "passive"))
      (node (ref "R24") (pin "1") (pinfunction "1_1") (pintype "passive"))
      (node (ref "R25") (pin "1") (pinfunction "1_1") (pintype "passive"))
    )
    (net (code "42") (name "Net-(D1-A)") (class "Default")
      (node (ref "D1") (pin "1") (pinfunction "A_1") (pintype "passive"))
      (node (ref "R1") (pin "1") (pinfunction "1_1") (pintype "passive"))
    )
    (net (code "43") (name "Net-(D2-A)") (class "Default")
      (node (ref "D2") (pin "1") (pinfunction "A_1") (pintype "passive"))
      (node (ref "R5") (pin "1") (pinfunction "1_1") (pintype "passive"))
    )
    (net (code "44") (name "Net-(D7-A)") (class "Default")
      (node (ref "D7") (pin "1") (pinfunction "A_1") (pintype "passive"))
      (node (ref "R18") (pin "1") (pinfunction "1_1") (pintype "passive"))
    )
    (net (code "45") (name "Net-(D8-K)") (class "Default")
      (node (ref "C31") (pin "1") (pinfunction "1_1") (pintype "passive"))
      (node (ref "C32") (pin "1") (pinfunction "1_1") (pintype "passive"))
      (node (ref "C33") (pin "1") (pinfunction "1_1") (pintype "passive"))
      (node (ref "D8") (pin "1") (pinfunction "K_1") (pintype "passive"))
      (node (ref "R19") (pin "1") (pinfunction "1_1") (pintype "passive"))
      (node (ref "R20") (pin "1") (pinfunction "1_1") (pintype "passive"))
      (node (ref "U7") (pin "5") (pinfunction "VIN_5") (pintype "passive"))
    )
    (net (code "46") (name "Net-(D9-K)") (class "Default")
      (node (ref "C30") (pin "2") (pinfunction "2_2") (pintype "passive"))
      (node (ref "D9") (pin "1") (pinfunction "K_1") (pintype "passive"))
      (node (ref "L2") (pin "1") (pinfunction "1_1") (pintype "passive"))
      (node (ref "U7") (pin "6") (pinfunction "SW_6") (pintype "passive"))
    )
    (net (code "47") (name "Net-(D10-C)") (class "Default")
      (node (ref "D10") (pin "1") (pinfunction "C_1") (pintype "passive"))
      (node (ref "D8") (pin "2") (pinfunction "A_2") (pintype "passive"))
      (node (ref "F1") (pin "2") (pinfunction "2_2") (pintype "passive"))
    )
    (net (code "48") (name "Net-(D11-A)") (class "Default")
      (node (ref "D11") (pin "1") (pinfunction "A_1") (pintype "passive"))
      (node (ref "R20") (pin "2") (pinfunction "2_2") (pintype "passive"))
    )
    (net (code "49") (name "Net-(D12-A)") (class "Default")
      (node (ref "D12") (pin "1") (pinfunction "A_1") (pintype "passive"))
      (node (ref "R22") (pin "2") (pinfunction "2_2") (pintype "passive"))
    )
    (net (code "50") (name "Net-(D13-C)") (class "Default")
      (node (ref "D13") (pin "1") (pinfunction "C_1") (pintype "passive"))
      (node (ref "F2") (pin "2") (pinfunction "2_2") (pintype "passive"))
      (node (ref "L3") (pin "4") (pinfunction "4_4") (pintype "passive"))
      (node (ref "R2") (pin "2") (pinfunction "2_2") (pintype "passive"))
    )
    (net (code "51") (name "Net-(D14-C)") (class "Default")
      (node (ref "D14") (pin "1") (pinfunction "C_1") (pintype "passive"))
      (node (ref "F3") (pin "2") (pinfunction "2_2") (pintype "passive"))
      (node (ref "L3") (pin "1") (pinfunction "1_1") (pintype "passive"))
      (node (ref "R4") (pin "2") (pinfunction "2_2") (pintype "passive"))
    )
    (net (code "52") (name "Net-(D15-C)") (class "Default")
      (node (ref "D15") (pin "1") (pinfunction "C_1") (pintype "passive"))
      (node (ref "F4") (pin "2") (pinfunction "2_2") (pintype "passive"))
      (node (ref "L4") (pin "4") (pinfunction "4_4") (pintype "passive"))
      (node (ref "R24") (pin "2") (pinfunction "2_2") (pintype "passive"))
    )
    (net (code "53") (name "Net-(D16-C)") (class "Default")
      (node (ref "D16") (pin "1") (pinfunction "C_1") (pintype "passive"))
      (node (ref "F5") (pin "2") (pinfunction "2_2") (pintype "passive"))
      (node (ref "L4") (pin "1") (pinfunction "1_1") (pintype "passive"))
      (node (ref "R25") (pin "2") (pinfunction "2_2") (pintype "passive"))
    )
    (net (code "54") (name "Net-(J8-Pad1)") (class "Default")
      (node (ref "J8") (pin "1") (pinfunction "1_1") (pintype "power_in"))
      (node (ref "R8") (pin "1") (pinfunction "1_1") (pintype "passive"))
    )
    (net (code "55") (name "Net-(Q1-B)") (class "Default")
      (node (ref "Q1") (pin "1") (pinfunction "B_1") (pintype "passive"))
      (node (ref "R8") (pin "2") (pinfunction "2_2") (pintype "passive"))
    )
    (net (code "56") (name "Net-(T1-B)") (class "Default")
      (node (ref "C11") (pin "2") (pinfunction "2_2") (pintype "passive"))
      (node (ref "R17") (pin "2") (pinfunction "2_2") (pintype "passive"))
      (node (ref "R9") (pin "2") (pinfunction "2_2") (pintype "passive"))
      (node (ref "T1") (pin "1") (pinfunction "B_1") (pintype "passive"))
    )
    (net (code "57") (name "Net-(T1-C)") (class "Default")
      (node (ref "J13") (pin "2") (pinfunction "2_2") (pintype "passive"))
      (node (ref "T1") (pin "3") (pinfunction "C_3") (pintype "passive"))
    )
    (net (code "58") (name "Net-(U1A-BOOT0)") (class "Default")
      (node (ref "R3") (pin "2") (pinfunction "2_2") (pintype "passive"))
      (node (ref "U1") (pin "60") (pinfunction "BOOT0_60") (pintype "passive"))
    )
    (net (code "59") (name "Net-(U1A-PH0{slash}RCC_OSC_IN)") (class "Default")
      (node (ref "C6") (pin "2") (pinfunction "2_2") (pintype "passive"))
      (node (ref "U1") (pin "5") (pinfunction "PH0/RCC_OSC_IN_5") (pintype "passive"))
      (node (ref "X1") (pin "3") (pinfunction "OUTPUT_3") (pintype "passive"))
    )
    (net (code "60") (name "Net-(U1A-VCAP_1)") (class "Default")
      (node (ref "C9") (pin "2") (pinfunction "2_2") (pintype "passive"))
      (node (ref "U1") (pin "31") (pinfunction "VCAP_1_31") (pintype "passive"))
    )
    (net (code "61") (name "Net-(U1A-VCAP_2)") (class "Default")
      (node (ref "C8") (pin "2") (pinfunction "2_2") (pintype "passive"))
      (node (ref "U1") (pin "47") (pinfunction "VCAP_2_47") (pintype "passive"))
    )
    (net (code "62") (name "Net-(U1A-VDDA)") (class "Default")
      (node (ref "C22") (pin "2") (pinfunction "2_2") (pintype "passive"))
      (node (ref "L1") (pin "2") (pinfunction "2_2") (pintype "passive"))
      (node (ref "U1") (pin "13") (pinfunction "VDDA_13") (pintype "passive"))
    )
    (net (code "63") (name "Net-(U4-CANH)") (class "Default")
      (node (ref "F2") (pin "1") (pinfunction "1_1") (pintype "passive"))
      (node (ref "U4") (pin "7") (pinfunction "CANH_7") (pintype "passive"))
    )
    (net (code "64") (name "Net-(U4-CANL)") (class "Default")
      (node (ref "F3") (pin "1") (pinfunction "1_1") (pintype "passive"))
      (node (ref "U4") (pin "6") (pinfunction "CANL_6") (pintype "passive"))
    )
    (net (code "65") (name "Net-(U7-CB)") (class "Default")
      (node (ref "C30") (pin "1") (pinfunction "1_1") (pintype "passive"))
      (node (ref "U7") (pin "1") (pinfunction "CB_1") (pintype "passive"))
    )
    (net (code "66") (name "Net-(U7-FB)") (class "Default")
      (node (ref "R21") (pin "2") (pinfunction "2_2") (pintype "passive"))
      (node (ref "R23") (pin "1") (pinfunction "1_1") (pintype "passive"))
      (node (ref "U7") (pin "3") (pinfunction "FB_3") (pintype "passive"))
    )
    (net (code "67") (name "Net-(U7-SHDN#)") (class "Default")
      (node (ref "R19") (pin "2") (pinfunction "2_2") (pintype "passive"))
      (node (ref "U7") (pin "4") (pinfunction "SHDN#_4") (pintype "passive"))
    )
    (net (code "68") (name "Net-(U8-CANH)") (class "Default")
      (node (ref "F4") (pin "1") (pinfunction "1_1") (pintype "passive"))
      (node (ref "U8") (pin "7") (pinfunction "CANH_7") (pintype "passive"))
    )
    (net (code "69") (name "Net-(U8-CANL)") (class "Default")
      (node (ref "F5") (pin "1") (pinfunction "1_1") (pintype "passive"))
      (node (ref "U8") (pin "6") (pinfunction "CANL_6") (pintype "passive"))
    )
    (net (code "70") (name "unconnected-(J1-Pad6)") (class "Default")
      (node (ref "J1") (pin "6") (pinfunction "6_6") (pintype "passive"))
    )
    (net (code "71") (name "unconnected-(U1B-PA8-Pad41)") (class "Default")
      (node (ref "U1") (pin "41") (pinfunction "PA8_41") (pintype "passive"))
    )
    (net (code "72") (name "unconnected-(U1B-PA9-Pad42)") (class "Default")
      (node (ref "U1") (pin "42") (pinfunction "PA9_42") (pintype "passive"))
    )
    (net (code "73") (name "unconnected-(U1B-PA10-Pad43)") (class "Default")
      (node (ref "U1") (pin "43") (pinfunction "PA10_43") (pintype "passive+no_connect"))
    )
    (net (code "74") (name "unconnected-(U1B-PB0-Pad26)") (class "Default")
      (node (ref "U1") (pin "26") (pinfunction "PB0_26") (pintype "passive"))
    )
    (net (code "75") (name "unconnected-(U1B-PB1-Pad27)") (class "Default")
      (node (ref "U1") (pin "27") (pinfunction "PB1_27") (pintype "passive"))
    )
    (net (code "76") (name "unconnected-(U1B-PB2-Pad28)") (class "Default")
      (node (ref "U1") (pin "28") (pinfunction "PB2_28") (pintype "passive"))
    )
    (net (code "77") (name "unconnected-(U1B-PB4-Pad56)") (class "Default")
      (node (ref "U1") (pin "56") (pinfunction "PB4_56") (pintype "passive"))
    )
    (net (code "78") (name "unconnected-(U1B-PB8-Pad61)") (class "Default")
      (node (ref "U1") (pin "61") (pinfunction "PB8_61") (pintype "passive"))
    )
    (net (code "79") (name "unconnected-(U1B-PB9-Pad62)") (class "Default")
      (node (ref "U1") (pin "62") (pinfunction "PB9_62") (pintype "passive"))
    )
    (net (code "80") (name "unconnected-(U1B-PB10-Pad29)") (class "Default")
      (node (ref "U1") (pin "29") (pinfunction "PB10_29") (pintype "open_collector"))
    )
    (net (code "81") (name "unconnected-(U1B-PB14-Pad35)") (class "Default")
      (node (ref "U1") (pin "35") (pinfunction "PB14_35") (pintype "open_collector"))
    )
    (net (code "82") (name "unconnected-(U1B-PB15-Pad36)") (class "Default")
      (node (ref "U1") (pin "36") (pinfunction "PB15_36") (pintype "open_collector"))
    )
    (net (code "83") (name "unconnected-(U1B-PC0-Pad8)") (class "Default")
      (node (ref "U1") (pin "8") (pinfunction "PC0_8") (pintype "passive"))
    )
    (net (code "84") (name "unconnected-(U1B-PC1-Pad9)") (class "Default")
      (node (ref "U1") (pin "9") (pinfunction "PC1_9") (pintype "passive"))
    )
    (net (code "85") (name "unconnected-(U1B-PC2-Pad10)") (class "Default")
      (node (ref "U1") (pin "10") (pinfunction "PC2_10") (pintype "passive"))
    )
    (net (code "86") (name "unconnected-(U1B-PC3-Pad11)") (class "Default")
      (node (ref "U1") (pin "11") (pinfunction "PC3_11") (pintype "passive"))
    )
    (net (code "87") (name "unconnected-(U1B-PC5-Pad25)") (class "Default")
      (node (ref "U1") (pin "25") (pinfunction "PC5_25") (pintype "passive"))
    )
    (net (code "88") (name "unconnected-(U1B-PC8-Pad39)") (class "Default")
      (node (ref "U1") (pin "39") (pinfunction "PC8_39") (pintype "passive"))
    )
    (net (code "89") (name "unconnected-(U1B-PC9-Pad40)") (class "Default")
      (node (ref "U1") (pin "40") (pinfunction "PC9_40") (pintype "passive"))
    )
    (net (code "90") (name "unconnected-(U1B-PC13-Pad2)") (class "Default")
      (node (ref "U1") (pin "2") (pinfunction "PC13_2") (pintype "passive+no_connect"))
    )
    (net (code "91") (name "unconnected-(U1B-PC14-Pad3)") (class "Default")
      (node (ref "U1") (pin "3") (pinfunction "PC14_3") (pintype "passive"))
    )
    (net (code "92") (name "unconnected-(U1B-PC15-Pad4)") (class "Default")
      (node (ref "U1") (pin "4") (pinfunction "PC15_4") (pintype "passive"))
    )
    (net (code "93") (name "unconnected-(U6-INT1-Pad16)") (class "Default")
      (node (ref "U6") (pin "16") (pinfunction "INT1_16") (pintype "passive"))
    )
    (net (code "94") (name "unconnected-(U6-INT2-Pad1)") (class "Default")
      (node (ref "U6") (pin "1") (pinfunction "INT2_1") (pintype "passive"))
    )
    (net (code "95") (name "unconnected-(U6-INT3-Pad12)") (class "Default")
      (node (ref "U6") (pin "12") (pinfunction "INT3_12") (pintype "passive"))
    )
    (net (code "96") (name "unconnected-(U6-INT4-Pad13)") (class "Default")
      (node (ref "U6") (pin "13") (pinfunction "INT4_13") (pintype "passive"))
    )
  )
)
